# Sheet1.net
KiCad netlist of a schematic drawn in Altium Designer
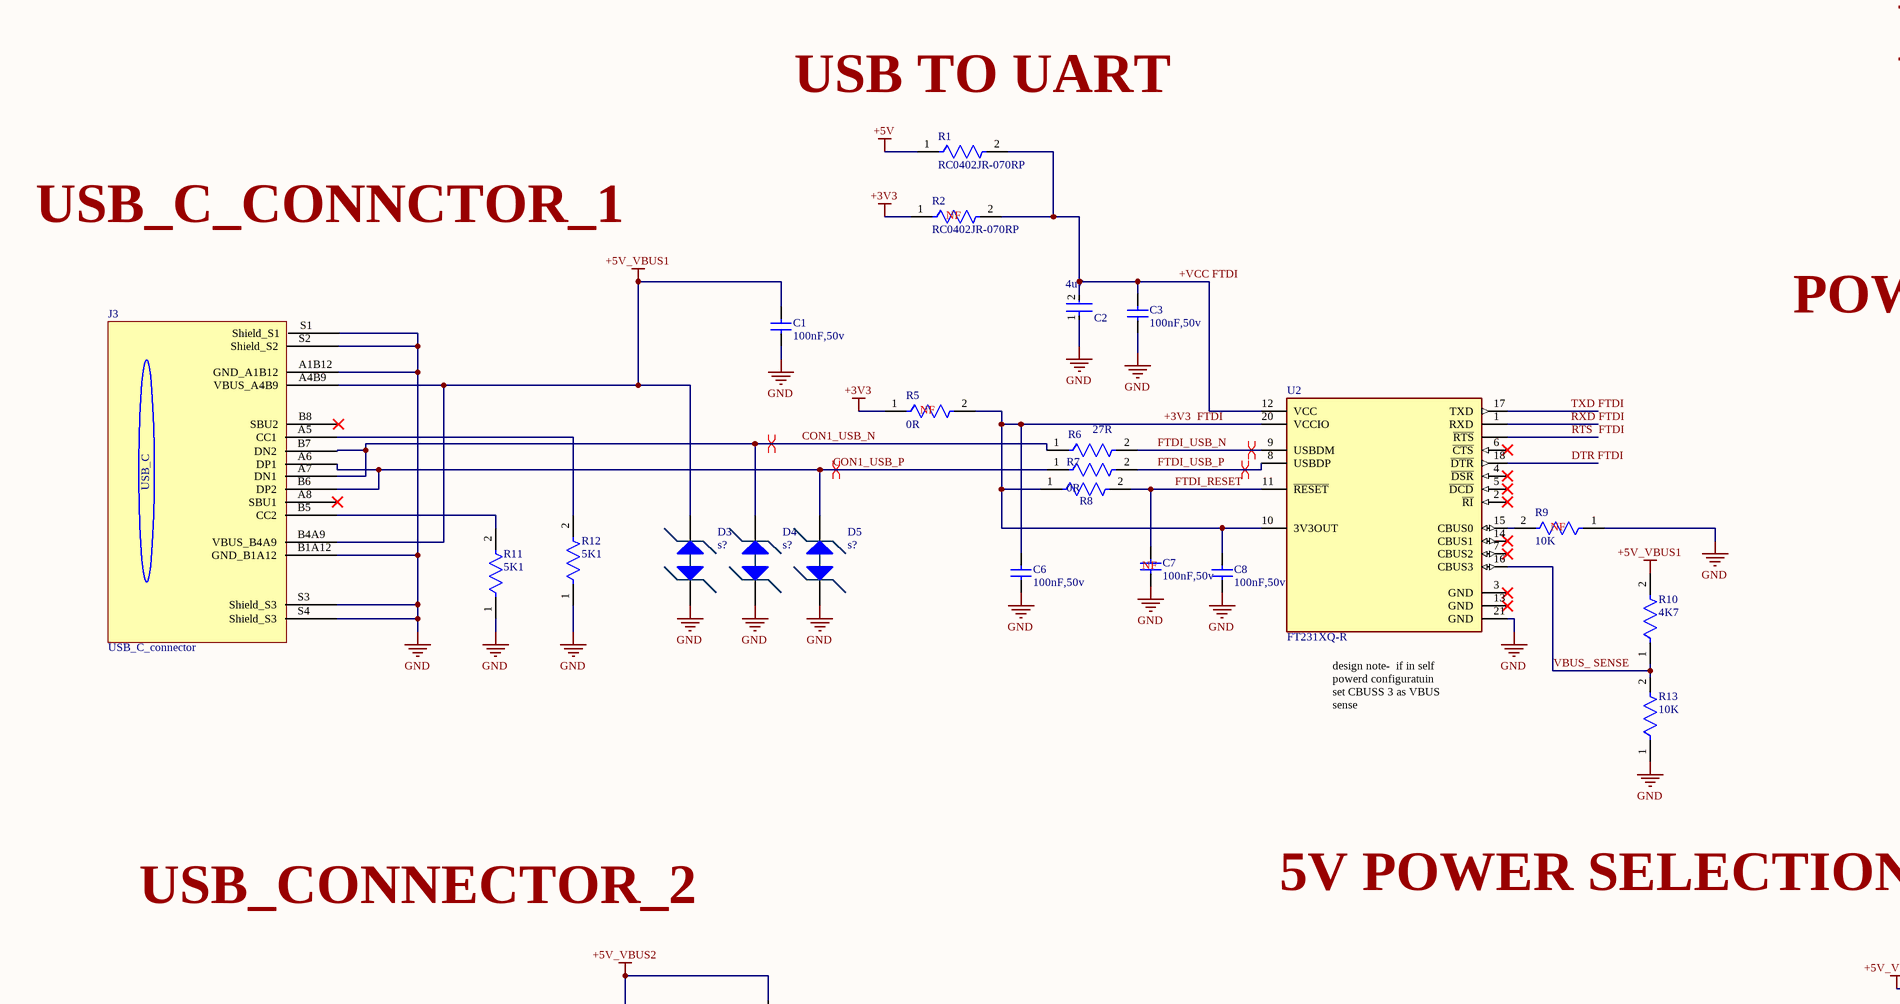
[diagram p0: Sheet1.SchDoc, top left]
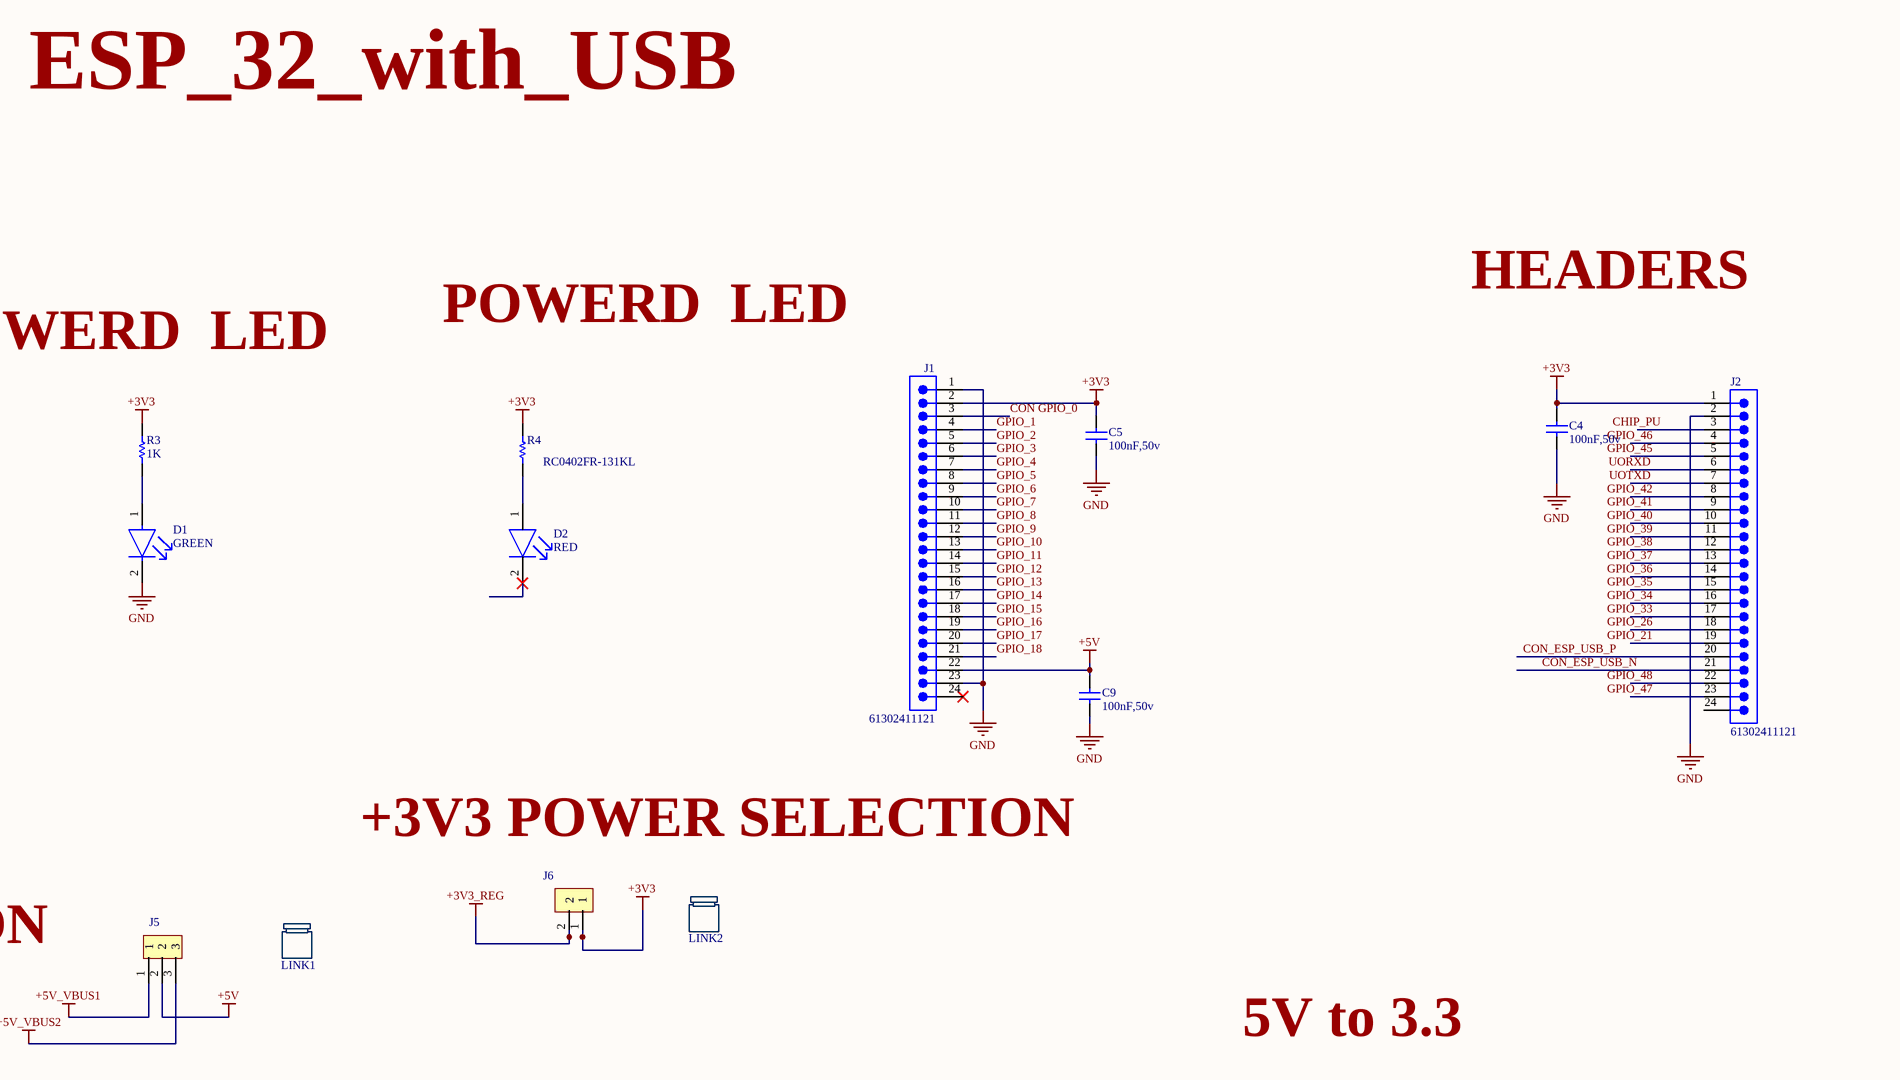
[diagram p1: Sheet1.SchDoc, top right]
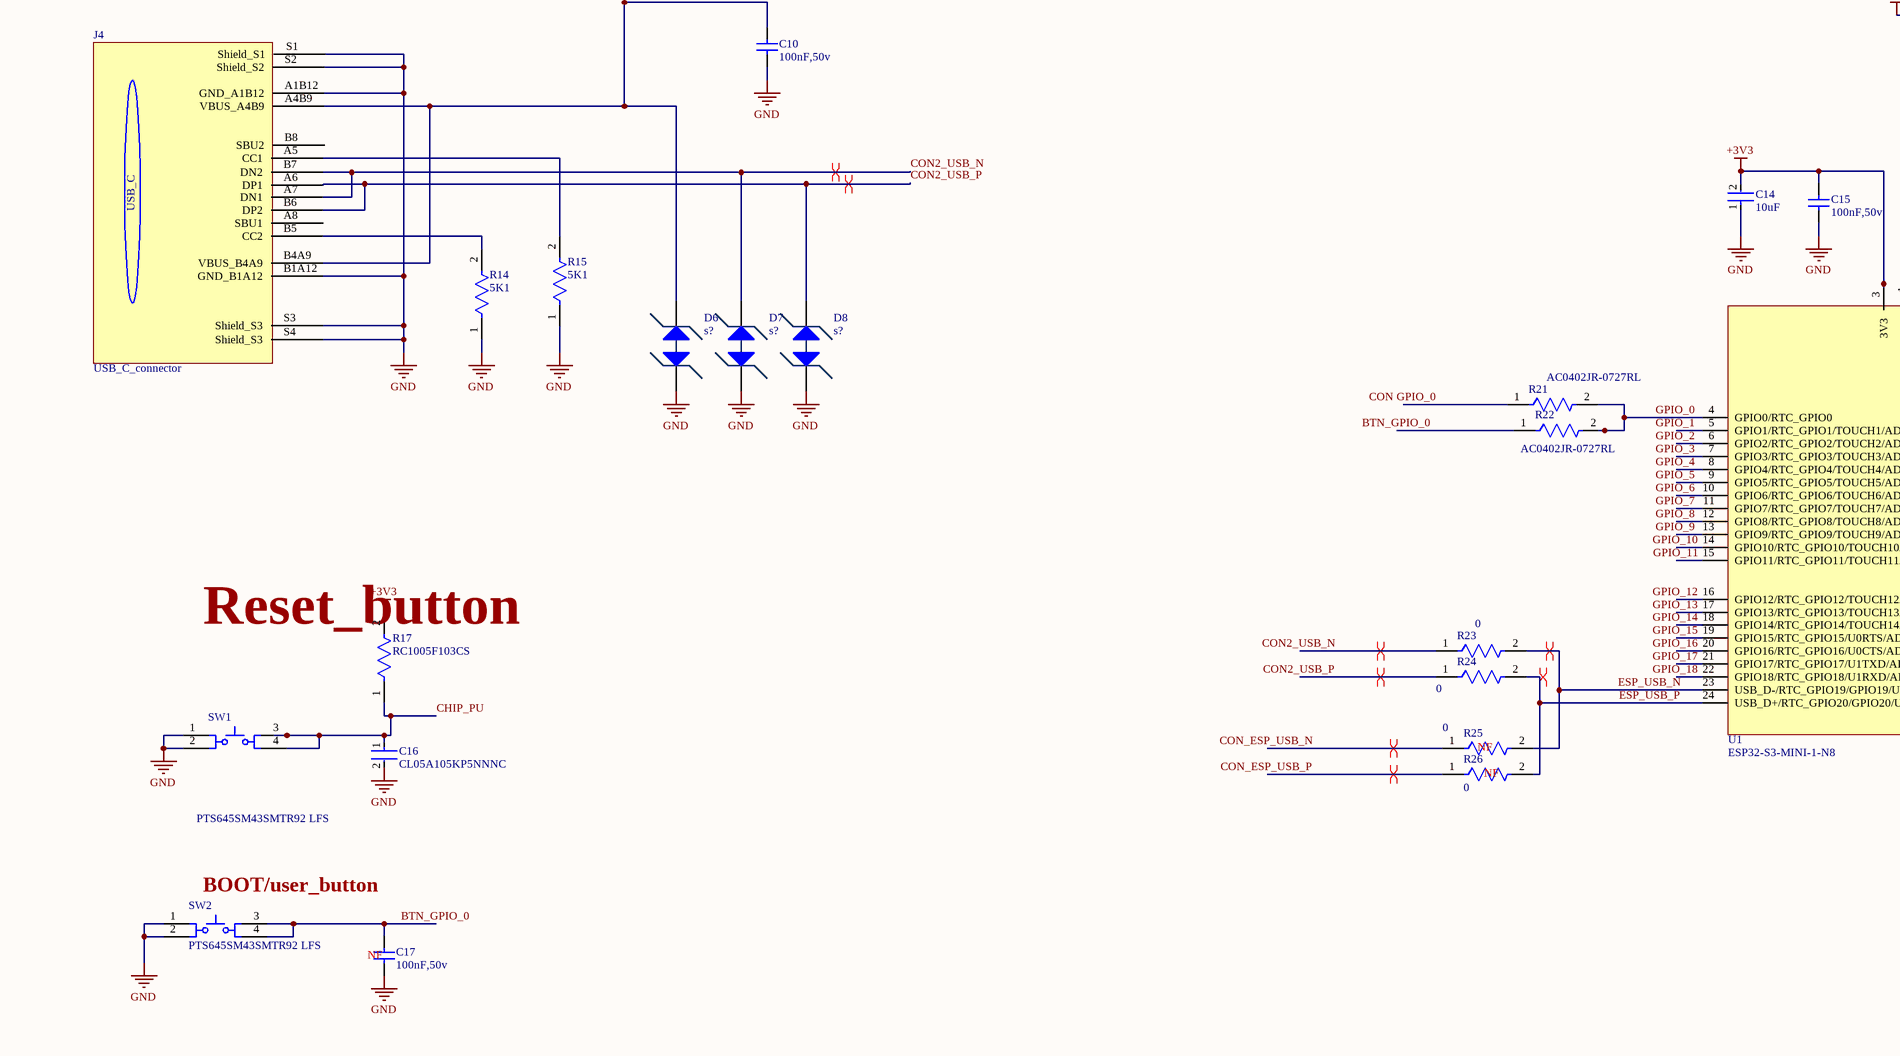
[diagram p2: Sheet1.SchDoc, bottom left]
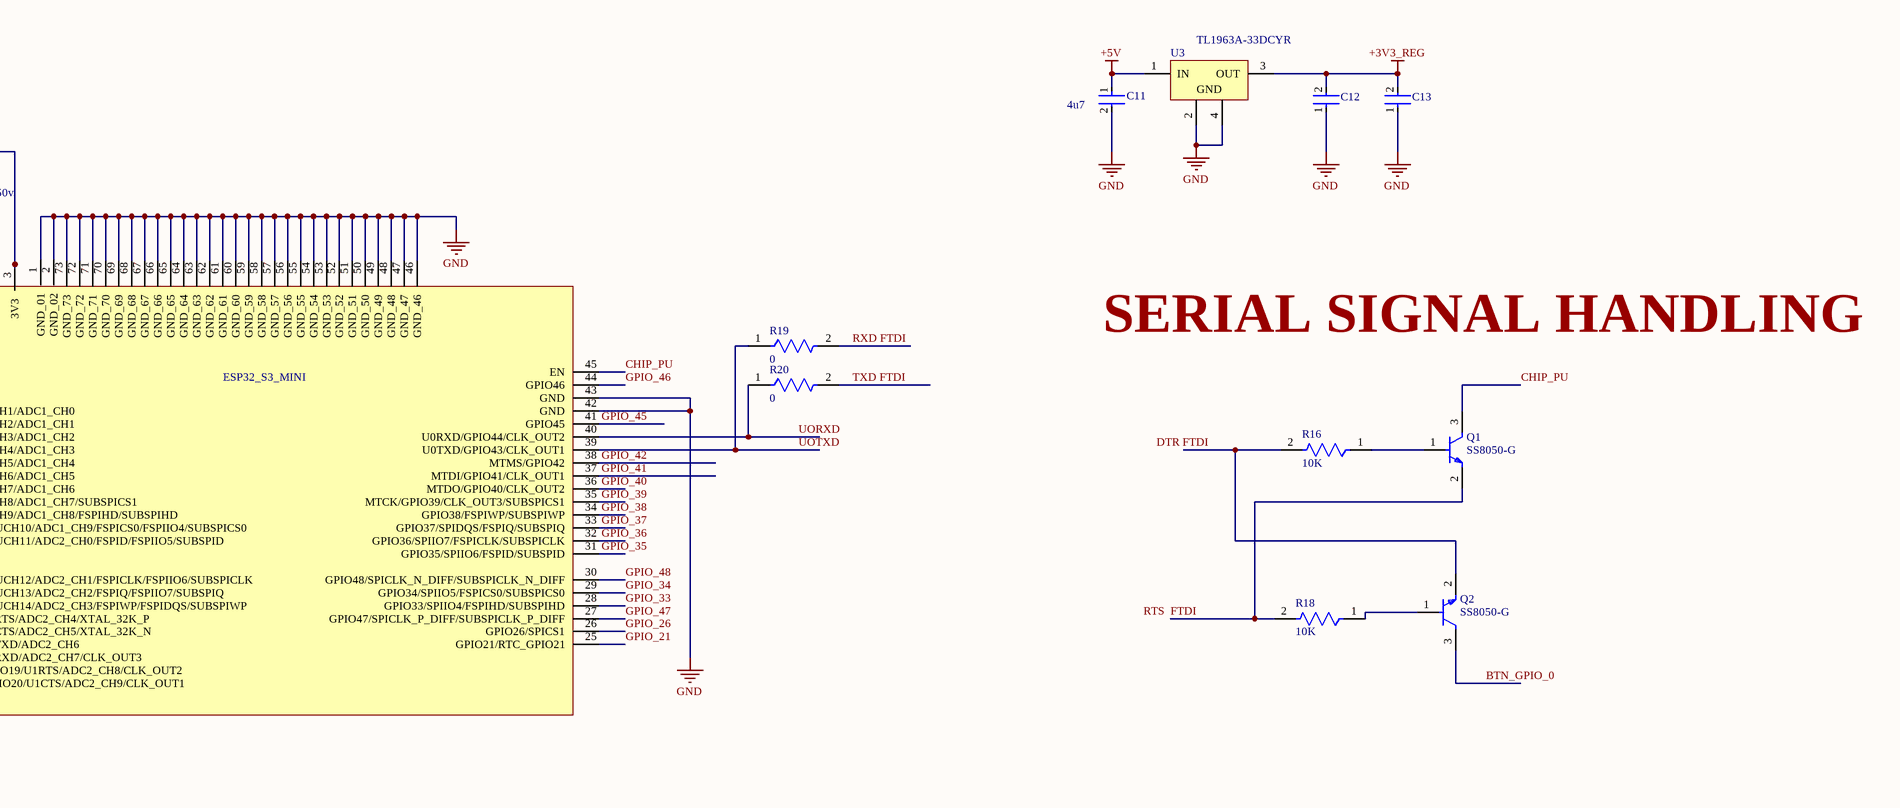
[diagram p3: Sheet1.SchDoc, bottom right]

(export (version "E")
  (design (tool "Eeschema 10.0.6"))
  (components
    (comp (ref "C1")
      (value "100nF,50v")
      (footprint "CAPC1005X55N")
      (fields
        (field (name "MANUFACTURER") "Samsung Electro-Mechanics")
        (field (name "MANUFACTURER PART NUMBER") "CL05B104KB54PNC")
        (field (name "TOLERANCE") "10%")
      )
      (libsource (lib "Schlib1") (part "CL05B104KB54PNC"))
    )
    (comp (ref "C2")
      (value "4u7")
      (footprint "FP-CL829-IPC_C")
      (description "Cap Ceramic 4.7uF 16V X5R ±20% SMD 0402 +85°C Paper T/R")
      (fields (field (name "TOLERANCE") "20%"))
      (libsource (lib "Altium Content Vault") (part "b4654b650e69147ec39a6b967a45e02"))
    )
    (comp (ref "C3")
      (value "100nF,50v")
      (footprint "CAPC1005X55N")
      (fields
        (field (name "MANUFACTURER") "Samsung Electro-Mechanics")
        (field (name "MANUFACTURER PART NUMBER") "CL05B104KB54PNC")
        (field (name "TOLERANCE") "10%")
      )
      (libsource (lib "Schlib1") (part "CL05B104KB54PNC"))
    )
    (comp (ref "C4")
      (value "100nF,50v")
      (footprint "CAPC1005X55N")
      (fields
        (field (name "MANUFACTURER") "Samsung Electro-Mechanics")
        (field (name "MANUFACTURER PART NUMBER") "CL05B104KB54PNC")
        (field (name "TOLERANCE") "10%")
      )
      (libsource (lib "Schlib1") (part "CL05B104KB54PNC"))
    )
    (comp (ref "C5")
      (value "100nF,50v")
      (footprint "CAPC1005X55N")
      (fields
        (field (name "MANUFACTURER") "Samsung Electro-Mechanics")
        (field (name "MANUFACTURER PART NUMBER") "CL05B104KB54PNC")
        (field (name "TOLERANCE") "10%")
      )
      (libsource (lib "Schlib1") (part "CL05B104KB54PNC"))
    )
    (comp (ref "C6")
      (value "100nF,50v")
      (footprint "CAPC1005X55N")
      (fields
        (field (name "MANUFACTURER") "Samsung Electro-Mechanics")
        (field (name "MANUFACTURER PART NUMBER") "CL05B104KB54PNC")
        (field (name "TOLERANCE") "10%")
      )
      (libsource (lib "Schlib1") (part "CL05B104KB54PNC"))
    )
    (comp (ref "C7")
      (value "100nF,50v")
      (footprint "CAPC1005X55N")
      (fields
        (field (name "MANUFACTURER") "Samsung Electro-Mechanics")
        (field (name "MANUFACTURER PART NUMBER") "CL05B104KB54PNC")
        (field (name "TOLERANCE") "10%")
      )
      (libsource (lib "Schlib1") (part "CL05B104KB54PNC"))
    )
    (comp (ref "C8")
      (value "100nF,50v")
      (footprint "CAPC1005X55N")
      (fields
        (field (name "MANUFACTURER") "Samsung Electro-Mechanics")
        (field (name "MANUFACTURER PART NUMBER") "CL05B104KB54PNC")
        (field (name "TOLERANCE") "10%")
      )
      (libsource (lib "Schlib1") (part "CL05B104KB54PNC"))
    )
    (comp (ref "C9")
      (value "100nF,50v")
      (footprint "CAPC1005X55N")
      (fields
        (field (name "MANUFACTURER") "Samsung Electro-Mechanics")
        (field (name "MANUFACTURER PART NUMBER") "CL05B104KB54PNC")
        (field (name "TOLERANCE") "10%")
      )
      (libsource (lib "Schlib1") (part "CL05B104KB54PNC"))
    )
    (comp (ref "C10")
      (value "100nF,50v")
      (footprint "CAPC1005X55N")
      (fields
        (field (name "MANUFACTURER") "Samsung Electro-Mechanics")
        (field (name "MANUFACTURER PART NUMBER") "CL05B104KB54PNC")
        (field (name "TOLERANCE") "10%")
      )
      (libsource (lib "Schlib1") (part "CL05B104KB54PNC"))
    )
    (comp (ref "C11")
      (value "4u7")
      (footprint "FP-CL829-IPC_C")
      (description "Cap Ceramic 4.7uF 16V X5R ±20% SMD 0402 +85°C Paper T/R")
      (fields (field (name "TOLERANCE") "20%"))
      (libsource (lib "Altium Content Vault") (part "b4654b650e69147ec39a6b967a45e02"))
    )
    (comp (ref "C12")
      (value "CL05A106MP8NUB8")
      (footprint "FP-CL07-IPC_C")
      (description "Cap Ceramic 10uF 10V X5R ±20% SMD 0402 +85°C Paper T/R")
      (fields (field (name "TOLERANCE") "20%"))
      (libsource (lib "Altium Content Vault") (part "b4654b650e69147ec39a6b967a45e02"))
    )
    (comp (ref "C13")
      (value "CL05A106MP8NUB8")
      (footprint "FP-CL07-IPC_C")
      (description "Cap Ceramic 10uF 10V X5R ±20% SMD 0402 +85°C Paper T/R")
      (fields (field (name "TOLERANCE") "20%"))
      (libsource (lib "Altium Content Vault") (part "b4654b650e69147ec39a6b967a45e02"))
    )
    (comp (ref "C14")
      (value "10uF")
      (footprint "FP-CL07-IPC_C")
      (description "Cap Ceramic 10uF 10V X5R ±20% SMD 0402 +85°C Paper T/R")
      (fields (field (name "TOLERANCE") "20%"))
      (libsource (lib "Altium Content Vault") (part "b4654b650e69147ec39a6b967a45e02"))
    )
    (comp (ref "C15")
      (value "100nF,50v")
      (footprint "CAPC1005X55N")
      (fields
        (field (name "MANUFACTURER") "Samsung Electro-Mechanics")
        (field (name "MANUFACTURER PART NUMBER") "CL05B104KB54PNC")
        (field (name "TOLERANCE") "10%")
      )
      (libsource (lib "Schlib1") (part "CL05B104KB54PNC"))
    )
    (comp (ref "C16")
      (value "CL05A105KP5NNNC")
      (footprint "FP-CL511-IPC_C")
      (description "Cap Ceramic 1uF 10V X5R ±10% SMD 0402 +85°C Paper T/R")
      (fields (field (name "TOLERANCE") "10%"))
      (libsource (lib "Altium Content Vault") (part "b4654b650e69147ec39a6b967a45e02"))
    )
    (comp (ref "C17")
      (value "100nF,50v")
      (footprint "CAPC1005X55N")
      (fields
        (field (name "MANUFACTURER") "Samsung Electro-Mechanics")
        (field (name "MANUFACTURER PART NUMBER") "CL05B104KB54PNC")
        (field (name "TOLERANCE") "10%")
      )
      (libsource (lib "Schlib1") (part "CL05B104KB54PNC"))
    )
    (comp (ref "D1")
      (value "GREEN")
      (footprint "FP-SM0402GC-MFG")
      (description "LED GREEN CLEAR 0402 SMD")
      (libsource (lib "Altium Content Vault") (part "ab1c01a81903e929fc6c44469aada92"))
    )
    (comp (ref "D2")
      (value "RED")
      (footprint "FP-SM0402RC-MFG")
      (description "LED RED CLEAR 0402 SMD")
      (libsource (lib "") (part "ab1c01a81903e929fc6c44469aada92_1"))
    )
    (comp (ref "D3") (value "s?") (footprint "SOD882") (libsource (lib "Schlib1") (part "AQ3045-01ETG")))
    (comp (ref "D4") (value "s?") (footprint "SOD882") (libsource (lib "Schlib1") (part "AQ3045-01ETG")))
    (comp (ref "D5") (value "s?") (footprint "SOD882") (libsource (lib "Schlib1") (part "AQ3045-01ETG")))
    (comp (ref "D6") (value "s?") (footprint "SOD882") (libsource (lib "Schlib1") (part "AQ3045-01ETG")))
    (comp (ref "D7") (value "s?") (footprint "SOD882") (libsource (lib "Schlib1") (part "AQ3045-01ETG")))
    (comp (ref "D8") (value "s?") (footprint "SOD882") (libsource (lib "Schlib1") (part "AQ3045-01ETG")))
    (comp (ref "J1")
      (value "61302411121")
      (footprint "61302411121")
      (description "THT Vertical Pin Header WR-PHD, Pitch 2.54 mm, Single Row, 24 pins")
      (libsource (lib "Altium Content Vault") (part "Header_Male_1R_24P"))
    )
    (comp (ref "J2")
      (value "61302411121")
      (footprint "61302411121")
      (description "THT Vertical Pin Header WR-PHD, Pitch 2.54 mm, Single Row, 24 pins")
      (libsource (lib "Altium Content Vault") (part "Header_Male_1R_24P"))
    )
    (comp (ref "J3")
      (value "USB_C_connector")
      (footprint "FP-2171790001-MFG")
      (fields (field (name "LCSC PART NUMBER") "C3197684"))
      (libsource (lib "Schlib1") (part "USB_C_connector"))
    )
    (comp (ref "J4")
      (value "USB_C_connector")
      (footprint "FP-2171790001-MFG")
      (fields (field (name "LCSC PART NUMBER") "C3197684"))
      (libsource (lib "Schlib1") (part "USB_C_connector"))
    )
    (comp (ref "J5")
      (value "FTS-103-01-F-S")
      (footprint "HDR_1X3_1.27MM")
      (fields (field (name "MANUFACTURER") "Samtec"))
      (libsource (lib "Schlib1") (part "FTS-103-01-F-S"))
    )
    (comp (ref "J6")
      (value "FTS-102-01-F-S")
      (footprint "HDR_1X2_1.27MM")
      (fields (field (name "MANUFACTURER") "Samtec"))
      (libsource (lib "Schlib1") (part "FTS-102-01-F-S"))
    )
    (comp (ref "LINK1")
      (value "M50-1920005")
      (fields (field (name "LCSC PART NUMBER") "C6986546"))
      (libsource (lib "Schlib1") (part "M50-1920005"))
    )
    (comp (ref "LINK2")
      (value "M50-1920005")
      (fields (field (name "LCSC PART NUMBER") "C6986546"))
      (libsource (lib "Schlib1") (part "M50-1920005"))
    )
    (comp (ref "Q1")
      (value "SS8050-G")
      (footprint "FP-SS8050-G-MFG")
      (description "NPN TRANSISTOR 1.5A 40V SOT-23 R")
      (libsource (lib "Altium Content Vault") (part "2a1388f82443b098dcd57d24ac7632d"))
    )
    (comp (ref "Q2")
      (value "SS8050-G")
      (footprint "FP-SS8050-G-MFG")
      (description "NPN TRANSISTOR 1.5A 40V SOT-23 R")
      (libsource (lib "Altium Content Vault") (part "2a1388f82443b098dcd57d24ac7632d"))
    )
    (comp (ref "R1")
      (value "RC0402JR-070RP")
      (footprint "FP-RC0402-0_4-MFG")
      (description "RES SMD 0 OHM JUMPER 1/16W 0402")
      (libsource (lib "Altium Content Vault") (part "1029c3af85768c4190bb7ad29bc67b5"))
    )
    (comp (ref "R2")
      (value "RC0402JR-070RP")
      (footprint "FP-RC0402-0_4-MFG")
      (description "RES SMD 0 OHM JUMPER 1/16W 0402")
      (libsource (lib "Altium Content Vault") (part "1029c3af85768c4190bb7ad29bc67b5"))
    )
    (comp (ref "R3")
      (value "1K")
      (footprint "RESC1005X40X25LL05T10")
      (fields (field (name "MANUFACTURER") "Yageo") (field (name "PART NUMBER") "RC0402FR-131KL"))
      (libsource (lib "Altium Content Vault") (part "RES"))
    )
    (comp (ref "R4")
      (value "RC0402FR-131KL")
      (footprint "RESC1005X40X25LL05T10")
      (fields (field (name "MANUFACTURER") "Yageo"))
      (libsource (lib "Altium Content Vault") (part "RES"))
    )
    (comp (ref "R5")
      (value "0R")
      (footprint "FP-RC0402-0_4-MFG")
      (description "RES SMD 0 OHM JUMPER 1/16W 0402")
      (libsource (lib "Altium Content Vault") (part "1029c3af85768c4190bb7ad29bc67b5"))
    )
    (comp (ref "R6")
      (value "27R")
      (footprint "FP-AC0402-MFG")
      (description "RES 27Ω ±5% 0.063W 0402")
      (fields (field (name "TOLERANCE") "5%"))
      (libsource (lib "Altium Content Vault") (part "1029c3af85768c4190bb7ad29bc67b5"))
    )
    (comp (ref "R7")
      (value "27R")
      (footprint "FP-AC0402-MFG")
      (description "RES 27Ω ±5% 0.063W 0402")
      (fields (field (name "TOLERANCE") "5%"))
      (libsource (lib "Altium Content Vault") (part "1029c3af85768c4190bb7ad29bc67b5"))
    )
    (comp (ref "R8")
      (value "0R")
      (footprint "FP-RC0402-0_4-MFG")
      (description "RES SMD 0 OHM JUMPER 1/16W 0402")
      (libsource (lib "Altium Content Vault") (part "1029c3af85768c4190bb7ad29bc67b5"))
    )
    (comp (ref "R9")
      (value "10K")
      (footprint "FP-CRGCQ0402-IPC_C")
      (description "CRGCQ 0402 10K 5%")
      (fields
        (field (name "TOLERANCE") "0.05")
        (field (name "OCTOPART") "https://octopart.com/crgcq0402j10k-te+connectivity-91017993")
      )
      (libsource (lib "Altium Content Vault") (part "1029c3af85768c4190bb7ad29bc67b5"))
    )
    (comp (ref "R10")
      (value "4K7")
      (footprint "FP-CRGP0402-IPC_C")
      (description "CRGP0402 4.7KΩ 0.125W ±100ppm/°C 1% 50V")
      (fields
        (field (name "OCTOPART") "https://octopart.com/crgp0402f4k7-te+connectivity-91018703")
        (field (name "MANUFACTURER") "TE")
      )
      (libsource (lib "Altium Content Vault") (part "1029c3af85768c4190bb7ad29bc67b5"))
    )
    (comp (ref "R11")
      (value "5K1")
      (footprint "FP-RC1005-MFG")
      (description "Res Thick Film 0402 5.1kΩ 5% 0.063W ±100ppm/°C Molded SMD T/R")
      (fields (field (name "TOLERANCE") "5%"))
      (libsource (lib "Altium Content Vault") (part "1029c3af85768c4190bb7ad29bc67b5"))
    )
    (comp (ref "R12")
      (value "5K1")
      (footprint "FP-RC1005-MFG")
      (description "Res Thick Film 0402 5.1kΩ 5% 0.063W ±100ppm/°C Molded SMD T/R")
      (fields (field (name "TOLERANCE") "5%"))
      (libsource (lib "Altium Content Vault") (part "1029c3af85768c4190bb7ad29bc67b5"))
    )
    (comp (ref "R13")
      (value "10K")
      (footprint "FP-CRGCQ0402-IPC_C")
      (description "CRGCQ 0402 10K 5%")
      (fields
        (field (name "TOLERANCE") "0.05")
        (field (name "OCTOPART") "https://octopart.com/crgcq0402j10k-te+connectivity-91017993")
      )
      (libsource (lib "Altium Content Vault") (part "1029c3af85768c4190bb7ad29bc67b5"))
    )
    (comp (ref "R14")
      (value "5K1")
      (footprint "FP-RC1005-MFG")
      (description "Res Thick Film 0402 5.1kΩ 5% 0.063W ±100ppm/°C Molded SMD T/R")
      (fields (field (name "TOLERANCE") "5%"))
      (libsource (lib "Altium Content Vault") (part "1029c3af85768c4190bb7ad29bc67b5"))
    )
    (comp (ref "R15")
      (value "5K1")
      (footprint "FP-RC1005-MFG")
      (description "Res Thick Film 0402 5.1kΩ 5% 0.063W ±100ppm/°C Molded SMD T/R")
      (fields (field (name "TOLERANCE") "5%"))
      (libsource (lib "Altium Content Vault") (part "1029c3af85768c4190bb7ad29bc67b5"))
    )
    (comp (ref "R16")
      (value "10K")
      (footprint "FP-CRGCQ0402-IPC_C")
      (description "CRGCQ 0402 10K 5%")
      (fields
        (field (name "TOLERANCE") "0.05")
        (field (name "OCTOPART") "https://octopart.com/crgcq0402j10k-te+connectivity-91017993")
      )
      (libsource (lib "Altium Content Vault") (part "1029c3af85768c4190bb7ad29bc67b5"))
    )
    (comp (ref "R17")
      (value "RC1005F103CS")
      (footprint "FP-RC1005-IPC_B")
      (description "Res Thick Film 0402 10kΩ 1% 0.063W ±100ppm/°C Molded SMD T/R")
      (fields (field (name "TOLERANCE") "1%"))
      (libsource (lib "Altium Content Vault") (part "1029c3af85768c4190bb7ad29bc67b5"))
    )
    (comp (ref "R18")
      (value "10K")
      (footprint "FP-CRGCQ0402-IPC_C")
      (description "CRGCQ 0402 10K 5%")
      (fields
        (field (name "TOLERANCE") "0.05")
        (field (name "OCTOPART") "https://octopart.com/crgcq0402j10k-te+connectivity-91017993")
      )
      (libsource (lib "Altium Content Vault") (part "1029c3af85768c4190bb7ad29bc67b5"))
    )
    (comp (ref "R19")
      (value "0")
      (footprint "FP-RC0402-0_4-MFG")
      (description "RES SMD 0 OHM JUMPER 1/16W 0402")
      (libsource (lib "Altium Content Vault") (part "1029c3af85768c4190bb7ad29bc67b5"))
    )
    (comp (ref "R20")
      (value "0")
      (footprint "FP-RC0402-0_4-MFG")
      (description "RES SMD 0 OHM JUMPER 1/16W 0402")
      (libsource (lib "Altium Content Vault") (part "1029c3af85768c4190bb7ad29bc67b5"))
    )
    (comp (ref "R21")
      (value "AC0402JR-0727RL")
      (footprint "FP-AC0402-MFG")
      (description "RES 27Ω ±5% 0.063W 0402")
      (fields (field (name "TOLERANCE") "5%"))
      (libsource (lib "Altium Content Vault") (part "1029c3af85768c4190bb7ad29bc67b5"))
    )
    (comp (ref "R22")
      (value "AC0402JR-0727RL")
      (footprint "FP-AC0402-MFG")
      (description "RES 27Ω ±5% 0.063W 0402")
      (fields (field (name "TOLERANCE") "5%"))
      (libsource (lib "Altium Content Vault") (part "1029c3af85768c4190bb7ad29bc67b5"))
    )
    (comp (ref "R23")
      (value "0")
      (footprint "FP-RC0402-0_4-MFG")
      (description "RES SMD 0 OHM JUMPER 1/16W 0402")
      (libsource (lib "Altium Content Vault") (part "1029c3af85768c4190bb7ad29bc67b5"))
    )
    (comp (ref "R24")
      (value "0")
      (footprint "FP-RC0402-0_4-MFG")
      (description "RES SMD 0 OHM JUMPER 1/16W 0402")
      (libsource (lib "Altium Content Vault") (part "1029c3af85768c4190bb7ad29bc67b5"))
    )
    (comp (ref "R25")
      (value "0")
      (footprint "FP-RC0402-0_4-MFG")
      (description "RES SMD 0 OHM JUMPER 1/16W 0402")
      (libsource (lib "Altium Content Vault") (part "1029c3af85768c4190bb7ad29bc67b5"))
    )
    (comp (ref "R26")
      (value "0")
      (footprint "FP-RC0402-0_4-MFG")
      (description "RES SMD 0 OHM JUMPER 1/16W 0402")
      (libsource (lib "Altium Content Vault") (part "1029c3af85768c4190bb7ad29bc67b5"))
    )
    (comp (ref "SW1")
      (value "PTS645SM43SMTR92 LFS")
      (footprint "CKCP-PTS645S_V")
      (description "Tact Switch, SPST-NO, 50 mA, -20 to 60 degC, 4-Pin SMD, RoHS, Tape and Reel")
      (fields (field (name "MANUFACTURER") "C&K Components"))
      (libsource (lib "Altium Content Vault") (part "SW-SPST-NO-4"))
    )
    (comp (ref "SW2")
      (value "PTS645SM43SMTR92 LFS")
      (footprint "CKCP-PTS645S_V")
      (description "Tact Switch, SPST-NO, 50 mA, -20 to 60 degC, 4-Pin SMD, RoHS, Tape and Reel")
      (fields (field (name "MANUFACTURER") "C&K Components"))
      (libsource (lib "Altium Content Vault") (part "SW-SPST-NO-4"))
    )
    (comp (ref "U1")
      (value "ESP32-S3-MINI-1-N8")
      (footprint "XCVR_ESP32-S3-MINI-1-N8")
      (description "20.5dBm ESP32-S3FN8 Chip 2.4GHz SMD WiFi Modules ROHS")
      (fields (field (name "MANUFACTURER") "Espressif Systems"))
      (libsource (lib "Schlib1") (part "ESP32-S3-MINI-1-N8"))
    )
    (comp (ref "U2")
      (value "FT231XQ-R")
      (footprint "FP-QFN-20-MFG")
      (description "IC USB SERIAL FULL UART 20QFN")
      (libsource (lib "Altium Content Vault") (part "1a58eaec777a01ae16a7011961d8d4e"))
    )
    (comp (ref "U3")
      (value "TL1963A-33DCYR")
      (footprint "DCY0004A_N")
      (fields (field (name "MANUFACTURER") "Texas Instruments"))
      (libsource (lib "Altium Content Vault") (part "TI-TL1963A-XXDCY4"))
    )
  )
  (nets
    (net (code "1") (name "+3V3") (class "Default")
      (node (ref "C14") (pin "2") (pinfunction "2_2") (pintype "passive"))
      (node (ref "C15") (pin "2") (pinfunction "2_2") (pintype "passive"))
      (node (ref "C4") (pin "2") (pinfunction "2_2") (pintype "passive"))
      (node (ref "C5") (pin "2") (pinfunction "2_2") (pintype "passive"))
      (node (ref "J1") (pin "2") (pinfunction "2_2") (pintype "passive"))
      (node (ref "J2") (pin "1") (pinfunction "1_1") (pintype "passive"))
      (node (ref "J6") (pin "1") (pinfunction "1_1") (pintype "passive"))
      (node (ref "R17") (pin "2") (pinfunction "2_2") (pintype "passive"))
      (node (ref "R2") (pin "1") (pinfunction "1_1") (pintype "passive"))
      (node (ref "R3") (pin "2") (pinfunction "2_2") (pintype "passive"))
      (node (ref "R4") (pin "2") (pinfunction "2_2") (pintype "passive"))
      (node (ref "R5") (pin "1") (pinfunction "1_1") (pintype "passive"))
      (node (ref "U1") (pin "3") (pinfunction "3V3_3") (pintype "passive"))
    )
    (net (code "2") (name "+3V3_REG") (class "Default")
      (node (ref "C12") (pin "2") (pinfunction "2_2") (pintype "passive"))
      (node (ref "C13") (pin "2") (pinfunction "2_2") (pintype "passive"))
      (node (ref "J6") (pin "2") (pinfunction "2_2") (pintype "passive"))
      (node (ref "U3") (pin "3") (pinfunction "OUT_3") (pintype "power_in"))
    )
    (net (code "3") (name "+5V") (class "Default")
      (node (ref "C11") (pin "1") (pinfunction "1_1") (pintype "passive"))
      (node (ref "C9") (pin "2") (pinfunction "2_2") (pintype "passive"))
      (node (ref "J1") (pin "22") (pinfunction "22_22") (pintype "passive"))
      (node (ref "J5") (pin "2") (pinfunction "2_2") (pintype "passive"))
      (node (ref "R1") (pin "1") (pinfunction "1_1") (pintype "passive"))
      (node (ref "U3") (pin "1") (pinfunction "IN_1") (pintype "power_in"))
    )
    (net (code "4") (name "+5V_VBUS1") (class "Default")
      (node (ref "C1") (pin "2") (pinfunction "2_2") (pintype "passive"))
      (node (ref "D3") (pin "2") (pinfunction "2_2") (pintype "passive"))
      (node (ref "J3") (pin "A4B9") (pinfunction "VBUS_A4B9_A4B9") (pintype "passive"))
      (node (ref "J3") (pin "B4A9") (pinfunction "VBUS_B4A9_B4A9") (pintype "passive"))
      (node (ref "J5") (pin "1") (pinfunction "1_1") (pintype "passive"))
      (node (ref "R10") (pin "2") (pinfunction "2_2") (pintype "passive"))
    )
    (net (code "5") (name "+5V_VBUS2") (class "Default")
      (node (ref "C10") (pin "2") (pinfunction "2_2") (pintype "passive"))
      (node (ref "D6") (pin "2") (pinfunction "2_2") (pintype "passive"))
      (node (ref "J4") (pin "A4B9") (pinfunction "VBUS_A4B9_A4B9") (pintype "passive"))
      (node (ref "J4") (pin "B4A9") (pinfunction "VBUS_B4A9_B4A9") (pintype "passive"))
      (node (ref "J5") (pin "3") (pinfunction "3_3") (pintype "passive"))
    )
    (net (code "6") (name "/+3V3  FTDI") (class "Default")
      (node (ref "C6") (pin "2") (pinfunction "2_2") (pintype "passive"))
      (node (ref "C8") (pin "2") (pinfunction "2_2") (pintype "passive"))
      (node (ref "R5") (pin "2") (pinfunction "2_2") (pintype "passive"))
      (node (ref "R8") (pin "1") (pinfunction "1_1") (pintype "passive"))
      (node (ref "U2") (pin "10") (pinfunction "3V3OUT_10") (pintype "passive"))
      (node (ref "U2") (pin "20") (pinfunction "VCCIO_20") (pintype "passive"))
    )
    (net (code "7") (name "/+VCC FTDI") (class "Default")
      (node (ref "C2") (pin "2") (pinfunction "2_2") (pintype "passive"))
      (node (ref "C3") (pin "2") (pinfunction "2_2") (pintype "passive"))
      (node (ref "R1") (pin "2") (pinfunction "2_2") (pintype "passive"))
      (node (ref "R2") (pin "2") (pinfunction "2_2") (pintype "passive"))
      (node (ref "U2") (pin "12") (pinfunction "VCC_12") (pintype "power_in"))
    )
    (net (code "8") (name "/BTN_GPIO_0") (class "Default")
      (node (ref "C17") (pin "2") (pinfunction "2_2") (pintype "passive"))
      (node (ref "Q2") (pin "3") (pinfunction "C_3") (pintype "passive"))
      (node (ref "R22") (pin "1") (pinfunction "1_1") (pintype "passive"))
      (node (ref "SW2") (pin "3") (pinfunction "3_3") (pintype "passive"))
      (node (ref "SW2") (pin "4") (pinfunction "4_4") (pintype "passive"))
    )
    (net (code "9") (name "/CHIP_PU") (class "Default")
      (node (ref "C16") (pin "1") (pinfunction "1_1") (pintype "passive"))
      (node (ref "J2") (pin "3") (pinfunction "3_3") (pintype "passive"))
      (node (ref "Q1") (pin "3") (pinfunction "C_3") (pintype "passive"))
      (node (ref "R17") (pin "1") (pinfunction "1_1") (pintype "passive"))
      (node (ref "SW1") (pin "3") (pinfunction "3_3") (pintype "passive"))
      (node (ref "SW1") (pin "4") (pinfunction "4_4") (pintype "passive"))
      (node (ref "U1") (pin "45") (pinfunction "EN_45") (pintype "passive"))
    )
    (net (code "10") (name "/CON GPIO_0") (class "Default")
      (node (ref "J1") (pin "3") (pinfunction "3_3") (pintype "passive"))
      (node (ref "R21") (pin "1") (pinfunction "1_1") (pintype "passive"))
    )
    (net (code "11") (name "/CON1_USB_N") (class "Default")
      (node (ref "D4") (pin "2") (pinfunction "2_2") (pintype "passive"))
      (node (ref "J3") (pin "A7") (pinfunction "DN1_A7") (pintype "passive"))
      (node (ref "J3") (pin "B7") (pinfunction "DN2_B7") (pintype "passive"))
      (node (ref "R6") (pin "1") (pinfunction "1_1") (pintype "passive"))
    )
    (net (code "12") (name "/CON1_USB_P") (class "Default")
      (node (ref "D5") (pin "2") (pinfunction "2_2") (pintype "passive"))
      (node (ref "J3") (pin "A6") (pinfunction "DP1_A6") (pintype "passive"))
      (node (ref "J3") (pin "B6") (pinfunction "DP2_B6") (pintype "passive"))
      (node (ref "R7") (pin "1") (pinfunction "1_1") (pintype "passive"))
    )
    (net (code "13") (name "/CON2_USB_N") (class "Default")
      (node (ref "D7") (pin "2") (pinfunction "2_2") (pintype "passive"))
      (node (ref "J4") (pin "A7") (pinfunction "DN1_A7") (pintype "passive"))
      (node (ref "J4") (pin "B7") (pinfunction "DN2_B7") (pintype "passive"))
      (node (ref "R23") (pin "1") (pinfunction "1_1") (pintype "passive"))
    )
    (net (code "14") (name "/CON2_USB_P") (class "Default")
      (node (ref "D8") (pin "2") (pinfunction "2_2") (pintype "passive"))
      (node (ref "J4") (pin "A6") (pinfunction "DP1_A6") (pintype "passive"))
      (node (ref "J4") (pin "B6") (pinfunction "DP2_B6") (pintype "passive"))
      (node (ref "R24") (pin "1") (pinfunction "1_1") (pintype "passive"))
    )
    (net (code "15") (name "/CON_ESP_USB_N") (class "Default")
      (node (ref "J2") (pin "21") (pinfunction "21_21") (pintype "passive"))
      (node (ref "R25") (pin "1") (pinfunction "1_1") (pintype "passive"))
    )
    (net (code "16") (name "/CON_ESP_USB_P") (class "Default")
      (node (ref "J2") (pin "20") (pinfunction "20_20") (pintype "passive"))
      (node (ref "R26") (pin "1") (pinfunction "1_1") (pintype "passive"))
    )
    (net (code "17") (name "/DTR FTDI") (class "Default")
      (node (ref "Q2") (pin "2") (pinfunction "E_2") (pintype "passive"))
      (node (ref "R16") (pin "2") (pinfunction "2_2") (pintype "passive"))
      (node (ref "U2") (pin "18") (pinfunction "~{DTR}_18") (pintype "output"))
    )
    (net (code "18") (name "/ESP_USB_N") (class "Default")
      (node (ref "R23") (pin "2") (pinfunction "2_2") (pintype "passive"))
      (node (ref "R25") (pin "2") (pinfunction "2_2") (pintype "passive"))
      (node (ref "U1") (pin "23") (pinfunction "USB_D-/RTC_GPIO19/GPIO19/U1RTS/ADC2_CH8/CLK_OUT2_23") (pintype "passive"))
    )
    (net (code "19") (name "/ESP_USB_P") (class "Default")
      (node (ref "R24") (pin "2") (pinfunction "2_2") (pintype "passive"))
      (node (ref "R26") (pin "2") (pinfunction "2_2") (pintype "passive"))
      (node (ref "U1") (pin "24") (pinfunction "USB_D+/RTC_GPIO20/GPIO20/U1CTS/ADC2_CH9/CLK_OUT1_24") (pintype "passive"))
    )
    (net (code "20") (name "/FTDI_RESET") (class "Default")
      (node (ref "C7") (pin "2") (pinfunction "2_2") (pintype "passive"))
      (node (ref "R8") (pin "2") (pinfunction "2_2") (pintype "passive"))
      (node (ref "U2") (pin "11") (pinfunction "~{RESET}_11") (pintype "passive"))
    )
    (net (code "21") (name "/FTDI_USB_N") (class "Default")
      (node (ref "R6") (pin "2") (pinfunction "2_2") (pintype "passive"))
      (node (ref "U2") (pin "9") (pinfunction "USBDM_9") (pintype "passive"))
    )
    (net (code "22") (name "/FTDI_USB_P") (class "Default")
      (node (ref "R7") (pin "2") (pinfunction "2_2") (pintype "passive"))
      (node (ref "U2") (pin "8") (pinfunction "USBDP_8") (pintype "passive"))
    )
    (net (code "23") (name "/GPIO_0") (class "Default")
      (node (ref "R21") (pin "2") (pinfunction "2_2") (pintype "passive"))
      (node (ref "R22") (pin "2") (pinfunction "2_2") (pintype "passive"))
      (node (ref "U1") (pin "4") (pinfunction "GPIO0/RTC_GPIO0_4") (pintype "passive"))
    )
    (net (code "24") (name "/GPIO_1") (class "Default")
      (node (ref "J1") (pin "4") (pinfunction "4_4") (pintype "passive"))
      (node (ref "U1") (pin "5") (pinfunction "GPIO1/RTC_GPIO1/TOUCH1/ADC1_CH0_5") (pintype "passive"))
    )
    (net (code "25") (name "/GPIO_2") (class "Default")
      (node (ref "J1") (pin "5") (pinfunction "5_5") (pintype "passive"))
      (node (ref "U1") (pin "6") (pinfunction "GPIO2/RTC_GPIO2/TOUCH2/ADC1_CH1_6") (pintype "passive"))
    )
    (net (code "26") (name "/GPIO_3") (class "Default")
      (node (ref "J1") (pin "6") (pinfunction "6_6") (pintype "passive"))
      (node (ref "U1") (pin "7") (pinfunction "GPIO3/RTC_GPIO3/TOUCH3/ADC1_CH2_7") (pintype "passive"))
    )
    (net (code "27") (name "/GPIO_4") (class "Default")
      (node (ref "J1") (pin "7") (pinfunction "7_7") (pintype "passive"))
      (node (ref "U1") (pin "8") (pinfunction "GPIO4/RTC_GPIO4/TOUCH4/ADC1_CH3_8") (pintype "passive"))
    )
    (net (code "28") (name "/GPIO_5") (class "Default")
      (node (ref "J1") (pin "8") (pinfunction "8_8") (pintype "passive"))
      (node (ref "U1") (pin "9") (pinfunction "GPIO5/RTC_GPIO5/TOUCH5/ADC1_CH4_9") (pintype "passive"))
    )
    (net (code "29") (name "/GPIO_6") (class "Default")
      (node (ref "J1") (pin "9") (pinfunction "9_9") (pintype "passive"))
      (node (ref "U1") (pin "10") (pinfunction "GPIO6/RTC_GPIO6/TOUCH6/ADC1_CH5_10") (pintype "passive"))
    )
    (net (code "30") (name "/GPIO_7") (class "Default")
      (node (ref "J1") (pin "10") (pinfunction "10_10") (pintype "passive"))
      (node (ref "U1") (pin "11") (pinfunction "GPIO7/RTC_GPIO7/TOUCH7/ADC1_CH6_11") (pintype "passive"))
    )
    (net (code "31") (name "/GPIO_8") (class "Default")
      (node (ref "J1") (pin "11") (pinfunction "11_11") (pintype "passive"))
      (node (ref "U1") (pin "12") (pinfunction "GPIO8/RTC_GPIO8/TOUCH8/ADC1_CH7/SUBSPICS1_12") (pintype "passive"))
    )
    (net (code "32") (name "/GPIO_9") (class "Default")
      (node (ref "J1") (pin "12") (pinfunction "12_12") (pintype "passive"))
      (node (ref "U1") (pin "13") (pinfunction "GPIO9/RTC_GPIO9/TOUCH9/ADC1_CH8/FSPIHD/SUBSPIHD_13") (pintype "passive"))
    )
    (net (code "33") (name "/GPIO_10") (class "Default")
      (node (ref "J1") (pin "13") (pinfunction "13_13") (pintype "passive"))
      (node (ref "U1") (pin "14") (pinfunction "GPIO10/RTC_GPIO10/TOUCH10/ADC1_CH9/FSPICS0/FSPIIO4/SUBSPICS0_14") (pintype "passive"))
    )
    (net (code "34") (name "/GPIO_11") (class "Default")
      (node (ref "J1") (pin "14") (pinfunction "14_14") (pintype "passive"))
      (node (ref "U1") (pin "15") (pinfunction "GPIO11/RTC_GPIO11/TOUCH11/ADC2_CH0/FSPID/FSPIIO5/SUBSPID_15") (pintype "passive"))
    )
    (net (code "35") (name "/GPIO_12") (class "Default")
      (node (ref "J1") (pin "15") (pinfunction "15_15") (pintype "passive"))
      (node (ref "U1") (pin "16") (pinfunction "GPIO12/RTC_GPIO12/TOUCH12/ADC2_CH1/FSPICLK/FSPIIO6/SUBSPICLK_16") (pintype "passive"))
    )
    (net (code "36") (name "/GPIO_13") (class "Default")
      (node (ref "J1") (pin "16") (pinfunction "16_16") (pintype "passive"))
      (node (ref "U1") (pin "17") (pinfunction "GPIO13/RTC_GPIO13/TOUCH13/ADC2_CH2/FSPIQ/FSPIIO7/SUBSPIQ_17") (pintype "passive"))
    )
    (net (code "37") (name "/GPIO_14") (class "Default")
      (node (ref "J1") (pin "17") (pinfunction "17_17") (pintype "passive"))
      (node (ref "U1") (pin "18") (pinfunction "GPIO14/RTC_GPIO14/TOUCH14/ADC2_CH3/FSPIWP/FSPIDQS/SUBSPIWP_18") (pintype "passive"))
    )
    (net (code "38") (name "/GPIO_15") (class "Default")
      (node (ref "J1") (pin "18") (pinfunction "18_18") (pintype "passive"))
      (node (ref "U1") (pin "19") (pinfunction "GPIO15/RTC_GPIO15/U0RTS/ADC2_CH4/XTAL_32K_P_19") (pintype "passive"))
    )
    (net (code "39") (name "/GPIO_16") (class "Default")
      (node (ref "J1") (pin "19") (pinfunction "19_19") (pintype "passive"))
      (node (ref "U1") (pin "20") (pinfunction "GPIO16/RTC_GPIO16/U0CTS/ADC2_CH5/XTAL_32K_N_20") (pintype "passive"))
    )
    (net (code "40") (name "/GPIO_17") (class "Default")
      (node (ref "J1") (pin "20") (pinfunction "20_20") (pintype "passive"))
      (node (ref "U1") (pin "21") (pinfunction "GPIO17/RTC_GPIO17/U1TXD/ADC2_CH6_21") (pintype "passive"))
    )
    (net (code "41") (name "/GPIO_18") (class "Default")
      (node (ref "J1") (pin "21") (pinfunction "21_21") (pintype "passive"))
      (node (ref "U1") (pin "22") (pinfunction "GPIO18/RTC_GPIO18/U1RXD/ADC2_CH7/CLK_OUT3_22") (pintype "passive"))
    )
    (net (code "42") (name "/GPIO_21") (class "Default")
      (node (ref "J2") (pin "19") (pinfunction "19_19") (pintype "passive"))
      (node (ref "U1") (pin "25") (pinfunction "GPIO21/RTC_GPIO21_25") (pintype "passive"))
    )
    (net (code "43") (name "/GPIO_26") (class "Default")
      (node (ref "J2") (pin "18") (pinfunction "18_18") (pintype "passive"))
      (node (ref "U1") (pin "26") (pinfunction "GPIO26/SPICS1_26") (pintype "passive"))
    )
    (net (code "44") (name "/GPIO_33") (class "Default")
      (node (ref "J2") (pin "17") (pinfunction "17_17") (pintype "passive"))
      (node (ref "U1") (pin "28") (pinfunction "GPIO33/SPIIO4/FSPIHD/SUBSPIHD_28") (pintype "passive"))
    )
    (net (code "45") (name "/GPIO_34") (class "Default")
      (node (ref "J2") (pin "16") (pinfunction "16_16") (pintype "passive"))
      (node (ref "U1") (pin "29") (pinfunction "GPIO34/SPIIO5/FSPICS0/SUBSPICS0_29") (pintype "passive"))
    )
    (net (code "46") (name "/GPIO_35") (class "Default")
      (node (ref "J2") (pin "15") (pinfunction "15_15") (pintype "passive"))
      (node (ref "U1") (pin "31") (pinfunction "GPIO35/SPIIO6/FSPID/SUBSPID_31") (pintype "passive"))
    )
    (net (code "47") (name "/GPIO_36") (class "Default")
      (node (ref "J2") (pin "14") (pinfunction "14_14") (pintype "passive"))
      (node (ref "U1") (pin "32") (pinfunction "GPIO36/SPIIO7/FSPICLK/SUBSPICLK_32") (pintype "passive"))
    )
    (net (code "48") (name "/GPIO_37") (class "Default")
      (node (ref "J2") (pin "13") (pinfunction "13_13") (pintype "passive"))
      (node (ref "U1") (pin "33") (pinfunction "GPIO37/SPIDQS/FSPIQ/SUBSPIQ_33") (pintype "passive"))
    )
    (net (code "49") (name "/GPIO_38") (class "Default")
      (node (ref "J2") (pin "12") (pinfunction "12_12") (pintype "passive"))
      (node (ref "U1") (pin "34") (pinfunction "GPIO38/FSPIWP/SUBSPIWP_34") (pintype "passive"))
    )
    (net (code "50") (name "/GPIO_39") (class "Default")
      (node (ref "J2") (pin "11") (pinfunction "11_11") (pintype "passive"))
      (node (ref "U1") (pin "35") (pinfunction "MTCK/GPIO39/CLK_OUT3/SUBSPICS1_35") (pintype "passive"))
    )
    (net (code "51") (name "/GPIO_40") (class "Default")
      (node (ref "J2") (pin "10") (pinfunction "10_10") (pintype "passive"))
      (node (ref "U1") (pin "36") (pinfunction "MTDO/GPIO40/CLK_OUT2_36") (pintype "passive"))
    )
    (net (code "52") (name "/GPIO_41") (class "Default")
      (node (ref "J2") (pin "9") (pinfunction "9_9") (pintype "passive"))
      (node (ref "U1") (pin "37") (pinfunction "MTDI/GPIO41/CLK_OUT1_37") (pintype "passive"))
    )
    (net (code "53") (name "/GPIO_42") (class "Default")
      (node (ref "J2") (pin "8") (pinfunction "8_8") (pintype "passive"))
      (node (ref "U1") (pin "38") (pinfunction "MTMS/GPIO42_38") (pintype "passive"))
    )
    (net (code "54") (name "/GPIO_45") (class "Default")
      (node (ref "J2") (pin "5") (pinfunction "5_5") (pintype "passive"))
      (node (ref "U1") (pin "41") (pinfunction "GPIO45_41") (pintype "passive"))
    )
    (net (code "55") (name "/GPIO_46") (class "Default")
      (node (ref "J2") (pin "4") (pinfunction "4_4") (pintype "passive"))
      (node (ref "U1") (pin "44") (pinfunction "GPIO46_44") (pintype "passive"))
    )
    (net (code "56") (name "/GPIO_47") (class "Default")
      (node (ref "J2") (pin "23") (pinfunction "23_23") (pintype "passive"))
      (node (ref "U1") (pin "27") (pinfunction "GPIO47/SPICLK_P_DIFF/SUBSPICLK_P_DIFF_27") (pintype "passive"))
    )
    (net (code "57") (name "/GPIO_48") (class "Default")
      (node (ref "J2") (pin "22") (pinfunction "22_22") (pintype "passive"))
      (node (ref "U1") (pin "30") (pinfunction "GPIO48/SPICLK_N_DIFF/SUBSPICLK_N_DIFF_30") (pintype "passive"))
    )
    (net (code "58") (name "/RTS  FTDI") (class "Default")
      (node (ref "Q1") (pin "2") (pinfunction "E_2") (pintype "passive"))
      (node (ref "R18") (pin "2") (pinfunction "2_2") (pintype "passive"))
      (node (ref "U2") (pin "19") (pinfunction "~{RTS}_19") (pintype "passive"))
    )
    (net (code "59") (name "/RXD FTDI") (class "Default")
      (node (ref "R19") (pin "2") (pinfunction "2_2") (pintype "passive"))
      (node (ref "U2") (pin "1") (pinfunction "RXD_1") (pintype "passive"))
    )
    (net (code "60") (name "/TXD FTDI") (class "Default")
      (node (ref "R20") (pin "2") (pinfunction "2_2") (pintype "passive"))
      (node (ref "U2") (pin "17") (pinfunction "TXD_17") (pintype "output"))
    )
    (net (code "61") (name "/UORXD") (class "Default")
      (node (ref "J2") (pin "6") (pinfunction "6_6") (pintype "passive"))
      (node (ref "R20") (pin "1") (pinfunction "1_1") (pintype "passive"))
      (node (ref "U1") (pin "40") (pinfunction "U0RXD/GPIO44/CLK_OUT2_40") (pintype "passive"))
    )
    (net (code "62") (name "/UOTXD") (class "Default")
      (node (ref "J2") (pin "7") (pinfunction "7_7") (pintype "passive"))
      (node (ref "R19") (pin "1") (pinfunction "1_1") (pintype "passive"))
      (node (ref "U1") (pin "39") (pinfunction "U0TXD/GPIO43/CLK_OUT1_39") (pintype "passive"))
    )
    (net (code "63") (name "/VBUS_ SENSE") (class "Default")
      (node (ref "R10") (pin "1") (pinfunction "1_1") (pintype "passive"))
      (node (ref "R13") (pin "2") (pinfunction "2_2") (pintype "passive"))
      (node (ref "U2") (pin "16") (pinfunction "CBUS3_16") (pintype "bidirectional"))
    )
    (net (code "64") (name "GND") (class "Default")
      (node (ref "C1") (pin "1") (pinfunction "1_1") (pintype "passive"))
      (node (ref "C10") (pin "1") (pinfunction "1_1") (pintype "passive"))
      (node (ref "C11") (pin "2") (pinfunction "2_2") (pintype "passive"))
      (node (ref "C12") (pin "1") (pinfunction "1_1") (pintype "passive"))
      (node (ref "C13") (pin "1") (pinfunction "1_1") (pintype "passive"))
      (node (ref "C14") (pin "1") (pinfunction "1_1") (pintype "passive"))
      (node (ref "C15") (pin "1") (pinfunction "1_1") (pintype "passive"))
      (node (ref "C16") (pin "2") (pinfunction "2_2") (pintype "passive"))
      (node (ref "C17") (pin "1") (pinfunction "1_1") (pintype "passive"))
      (node (ref "C2") (pin "1") (pinfunction "1_1") (pintype "passive"))
      (node (ref "C3") (pin "1") (pinfunction "1_1") (pintype "passive"))
      (node (ref "C4") (pin "1") (pinfunction "1_1") (pintype "passive"))
      (node (ref "C5") (pin "1") (pinfunction "1_1") (pintype "passive"))
      (node (ref "C6") (pin "1") (pinfunction "1_1") (pintype "passive"))
      (node (ref "C7") (pin "1") (pinfunction "1_1") (pintype "passive"))
      (node (ref "C8") (pin "1") (pinfunction "1_1") (pintype "passive"))
      (node (ref "C9") (pin "1") (pinfunction "1_1") (pintype "passive"))
      (node (ref "D1") (pin "2") (pinfunction "C_2") (pintype "passive"))
      (node (ref "D3") (pin "1") (pinfunction "1_1") (pintype "passive"))
      (node (ref "D4") (pin "1") (pinfunction "1_1") (pintype "passive"))
      (node (ref "D5") (pin "1") (pinfunction "1_1") (pintype "passive"))
      (node (ref "D6") (pin "1") (pinfunction "1_1") (pintype "passive"))
      (node (ref "D7") (pin "1") (pinfunction "1_1") (pintype "passive"))
      (node (ref "D8") (pin "1") (pinfunction "1_1") (pintype "passive"))
      (node (ref "J1") (pin "1") (pinfunction "1_1") (pintype "passive"))
      (node (ref "J1") (pin "23") (pinfunction "23_23") (pintype "passive"))
      (node (ref "J2") (pin "2") (pinfunction "2_2") (pintype "passive"))
      (node (ref "J3") (pin "A1B12") (pinfunction "GND_A1B12_A1B12") (pintype "passive"))
      (node (ref "J3") (pin "B1A12") (pinfunction "GND_B1A12_B1A12") (pintype "passive"))
      (node (ref "J3") (pin "S1") (pinfunction "Shield_S1_S1") (pintype "passive"))
      (node (ref "J3") (pin "S2") (pinfunction "Shield_S2_S2") (pintype "passive"))
      (node (ref "J3") (pin "S3") (pinfunction "Shield_S3_S3") (pintype "passive"))
      (node (ref "J3") (pin "S4") (pinfunction "Shield_S3_S4") (pintype "passive"))
      (node (ref "J4") (pin "A1B12") (pinfunction "GND_A1B12_A1B12") (pintype "passive"))
      (node (ref "J4") (pin "B1A12") (pinfunction "GND_B1A12_B1A12") (pintype "passive"))
      (node (ref "J4") (pin "S1") (pinfunction "Shield_S1_S1") (pintype "passive"))
      (node (ref "J4") (pin "S2") (pinfunction "Shield_S2_S2") (pintype "passive"))
      (node (ref "J4") (pin "S3") (pinfunction "Shield_S3_S3") (pintype "passive"))
      (node (ref "J4") (pin "S4") (pinfunction "Shield_S3_S4") (pintype "passive"))
      (node (ref "R11") (pin "1") (pinfunction "1_1") (pintype "passive"))
      (node (ref "R12") (pin "1") (pinfunction "1_1") (pintype "passive"))
      (node (ref "R13") (pin "1") (pinfunction "1_1") (pintype "passive"))
      (node (ref "R14") (pin "1") (pinfunction "1_1") (pintype "passive"))
      (node (ref "R15") (pin "1") (pinfunction "1_1") (pintype "passive"))
      (node (ref "R9") (pin "1") (pinfunction "1_1") (pintype "passive"))
      (node (ref "SW1") (pin "1") (pinfunction "1_1") (pintype "passive"))
      (node (ref "SW1") (pin "2") (pinfunction "2_2") (pintype "passive"))
      (node (ref "SW2") (pin "1") (pinfunction "1_1") (pintype "passive"))
      (node (ref "SW2") (pin "2") (pinfunction "2_2") (pintype "passive"))
      (node (ref "U1") (pin "1") (pinfunction "GND_01_1") (pintype "passive"))
      (node (ref "U1") (pin "2") (pinfunction "GND_02_2") (pintype "passive"))
      (node (ref "U1") (pin "42") (pinfunction "GND_42") (pintype "passive"))
      (node (ref "U1") (pin "43") (pinfunction "GND_43") (pintype "passive"))
      (node (ref "U1") (pin "46") (pinfunction "GND_46_46") (pintype "passive"))
      (node (ref "U1") (pin "47") (pinfunction "GND_47_47") (pintype "passive"))
      (node (ref "U1") (pin "48") (pinfunction "GND_48_48") (pintype "passive"))
      (node (ref "U1") (pin "49") (pinfunction "GND_49_49") (pintype "passive"))
      (node (ref "U1") (pin "50") (pinfunction "GND_50_50") (pintype "passive"))
      (node (ref "U1") (pin "51") (pinfunction "GND_51_51") (pintype "passive"))
      (node (ref "U1") (pin "52") (pinfunction "GND_52_52") (pintype "passive"))
      (node (ref "U1") (pin "53") (pinfunction "GND_53_53") (pintype "passive"))
      (node (ref "U1") (pin "54") (pinfunction "GND_54_54") (pintype "passive"))
      (node (ref "U1") (pin "55") (pinfunction "GND_55_55") (pintype "passive"))
      (node (ref "U1") (pin "56") (pinfunction "GND_56_56") (pintype "passive"))
      (node (ref "U1") (pin "57") (pinfunction "GND_57_57") (pintype "passive"))
      (node (ref "U1") (pin "58") (pinfunction "GND_58_58") (pintype "passive"))
      (node (ref "U1") (pin "59") (pinfunction "GND_59_59") (pintype "passive"))
      (node (ref "U1") (pin "60") (pinfunction "GND_60_60") (pintype "passive"))
      (node (ref "U1") (pin "61") (pinfunction "GND_61_61") (pintype "passive"))
      (node (ref "U1") (pin "62") (pinfunction "GND_62_62") (pintype "passive"))
      (node (ref "U1") (pin "63") (pinfunction "GND_63_63") (pintype "passive"))
      (node (ref "U1") (pin "64") (pinfunction "GND_64_64") (pintype "passive"))
      (node (ref "U1") (pin "65") (pinfunction "GND_65_65") (pintype "passive"))
      (node (ref "U1") (pin "66") (pinfunction "GND_66_66") (pintype "passive"))
      (node (ref "U1") (pin "67") (pinfunction "GND_67_67") (pintype "passive"))
      (node (ref "U1") (pin "68") (pinfunction "GND_68_68") (pintype "passive"))
      (node (ref "U1") (pin "69") (pinfunction "GND_69_69") (pintype "passive"))
      (node (ref "U1") (pin "70") (pinfunction "GND_70_70") (pintype "passive"))
      (node (ref "U1") (pin "71") (pinfunction "GND_71_71") (pintype "passive"))
      (node (ref "U1") (pin "72") (pinfunction "GND_72_72") (pintype "passive"))
      (node (ref "U1") (pin "73") (pinfunction "GND_73_73") (pintype "passive"))
      (node (ref "U2") (pin "21") (pinfunction "GND_21") (pintype "power_in"))
      (node (ref "U3") (pin "2") (pinfunction "GND_2") (pintype "power_in"))
      (node (ref "U3") (pin "4") (pinfunction "GND_4") (pintype "power_in"))
    )
    (net (code "65") (name "Net-(D1-A)") (class "Default")
      (node (ref "D1") (pin "1") (pinfunction "A_1") (pintype "passive"))
      (node (ref "R3") (pin "1") (pinfunction "1_1") (pintype "passive"))
    )
    (net (code "66") (name "Net-(D2-A)") (class "Default")
      (node (ref "D2") (pin "1") (pinfunction "A_1") (pintype "passive"))
      (node (ref "R4") (pin "1") (pinfunction "1_1") (pintype "passive"))
    )
    (net (code "67") (name "Net-(J3-CC1)") (class "Default")
      (node (ref "J3") (pin "A5") (pinfunction "CC1_A5") (pintype "passive"))
      (node (ref "R12") (pin "2") (pinfunction "2_2") (pintype "passive"))
    )
    (net (code "68") (name "Net-(J3-CC2)") (class "Default")
      (node (ref "J3") (pin "B5") (pinfunction "CC2_B5") (pintype "passive"))
      (node (ref "R11") (pin "2") (pinfunction "2_2") (pintype "passive"))
    )
    (net (code "69") (name "Net-(J4-CC1)") (class "Default")
      (node (ref "J4") (pin "A5") (pinfunction "CC1_A5") (pintype "passive"))
      (node (ref "R15") (pin "2") (pinfunction "2_2") (pintype "passive"))
    )
    (net (code "70") (name "Net-(J4-CC2)") (class "Default")
      (node (ref "J4") (pin "B5") (pinfunction "CC2_B5") (pintype "passive"))
      (node (ref "R14") (pin "2") (pinfunction "2_2") (pintype "passive"))
    )
    (net (code "71") (name "Net-(Q1-B)") (class "Default")
      (node (ref "Q1") (pin "1") (pinfunction "B_1") (pintype "passive"))
      (node (ref "R16") (pin "1") (pinfunction "1_1") (pintype "passive"))
    )
    (net (code "72") (name "Net-(Q2-B)") (class "Default")
      (node (ref "Q2") (pin "1") (pinfunction "B_1") (pintype "passive"))
      (node (ref "R18") (pin "1") (pinfunction "1_1") (pintype "passive"))
    )
    (net (code "73") (name "Net-(U2-CBUS0)") (class "Default")
      (node (ref "R9") (pin "2") (pinfunction "2_2") (pintype "passive"))
      (node (ref "U2") (pin "15") (pinfunction "CBUS0_15") (pintype "bidirectional"))
    )
    (net (code "74") (name "unconnected-(D2-C-Pad2)") (class "Default")
      (node (ref "D2") (pin "2") (pinfunction "C_2") (pintype "passive+no_connect"))
    )
    (net (code "75") (name "unconnected-(J1-Pad24)") (class "Default")
      (node (ref "J1") (pin "24") (pinfunction "24_24") (pintype "passive+no_connect"))
    )
    (net (code "76") (name "unconnected-(J2-Pad24)") (class "Default")
      (node (ref "J2") (pin "24") (pinfunction "24_24") (pintype "passive"))
    )
    (net (code "77") (name "unconnected-(J3-SBU1-PadA8)") (class "Default")
      (node (ref "J3") (pin "A8") (pinfunction "SBU1_A8") (pintype "passive+no_connect"))
    )
    (net (code "78") (name "unconnected-(J3-SBU2-PadB8)") (class "Default")
      (node (ref "J3") (pin "B8") (pinfunction "SBU2_B8") (pintype "passive+no_connect"))
    )
    (net (code "79") (name "unconnected-(J4-SBU1-PadA8)") (class "Default")
      (node (ref "J4") (pin "A8") (pinfunction "SBU1_A8") (pintype "passive"))
    )
    (net (code "80") (name "unconnected-(J4-SBU2-PadB8)") (class "Default")
      (node (ref "J4") (pin "B8") (pinfunction "SBU2_B8") (pintype "passive"))
    )
    (net (code "81") (name "unconnected-(U2-CBUS1-Pad14)") (class "Default")
      (node (ref "U2") (pin "14") (pinfunction "CBUS1_14") (pintype "bidirectional+no_connect"))
    )
    (net (code "82") (name "unconnected-(U2-CBUS2-Pad7)") (class "Default")
      (node (ref "U2") (pin "7") (pinfunction "CBUS2_7") (pintype "bidirectional+no_connect"))
    )
    (net (code "83") (name "unconnected-(U2-GND-Pad3)") (class "Default")
      (node (ref "U2") (pin "3") (pinfunction "GND_3") (pintype "power_in+no_connect"))
    )
    (net (code "84") (name "unconnected-(U2-GND-Pad13)") (class "Default")
      (node (ref "U2") (pin "13") (pinfunction "GND_13") (pintype "open_emitter+no_connect"))
    )
    (net (code "85") (name "unconnected-(U2-~{CTS}-Pad6)") (class "Default")
      (node (ref "U2") (pin "6") (pinfunction "~{CTS}_6") (pintype "input+no_connect"))
    )
    (net (code "86") (name "unconnected-(U2-~{DCD}-Pad5)") (class "Default")
      (node (ref "U2") (pin "5") (pinfunction "~{DCD}_5") (pintype "input+no_connect"))
    )
    (net (code "87") (name "unconnected-(U2-~{DSR}-Pad4)") (class "Default")
      (node (ref "U2") (pin "4") (pinfunction "~{DSR}_4") (pintype "input+no_connect"))
    )
    (net (code "88") (name "unconnected-(U2-~{RI}-Pad2)") (class "Default")
      (node (ref "U2") (pin "2") (pinfunction "~{RI}_2") (pintype "input+no_connect"))
    )
  )
)
